# EEPROM.net
KiCad netlist of a schematic drawn in Altium Designer
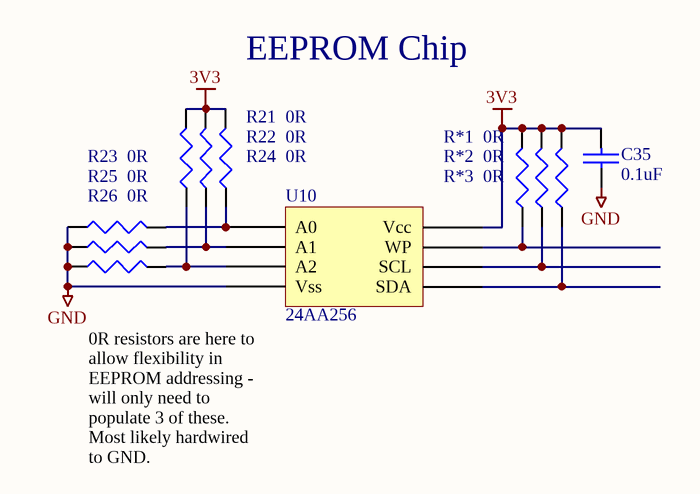
[diagram p0: EEPROM.SchDoc]

(export (version "E")
  (design (tool "Eeschema 10.0.6"))
  (components
    (comp (ref "C35")
      (value "0.1uF")
      (footprint "0805")
      (description "Capacitor")
      (libsource (lib "*") (part "CAP"))
    )
    (comp (ref "R*1")
      (value "0R")
      (footprint "0603")
      (description "Resistor")
      (libsource (lib "SunswiftLib20030312RR") (part "RES1"))
    )
    (comp (ref "R*2")
      (value "0R")
      (footprint "0603")
      (description "Resistor")
      (libsource (lib "SunswiftLib20030312RR") (part "RES1"))
    )
    (comp (ref "R*3")
      (value "0R")
      (footprint "0603")
      (description "Resistor")
      (libsource (lib "SunswiftLib20030312RR") (part "RES1"))
    )
    (comp (ref "R21")
      (value "0R")
      (footprint "0603")
      (description "Resistor")
      (libsource (lib "SunswiftLib20030312RR") (part "RES1"))
    )
    (comp (ref "R22")
      (value "0R")
      (footprint "0603")
      (description "Resistor")
      (libsource (lib "SunswiftLib20030312RR") (part "RES1"))
    )
    (comp (ref "R23")
      (value "0R")
      (footprint "0603")
      (description "Resistor")
      (libsource (lib "SunswiftLib20030312RR") (part "RES1"))
    )
    (comp (ref "R24")
      (value "0R")
      (footprint "0603")
      (description "Resistor")
      (libsource (lib "SunswiftLib20030312RR") (part "RES1"))
    )
    (comp (ref "R25")
      (value "0R")
      (footprint "0603")
      (description "Resistor")
      (libsource (lib "SunswiftLib20030312RR") (part "RES1"))
    )
    (comp (ref "R26")
      (value "0R")
      (footprint "0603")
      (description "Resistor")
      (libsource (lib "SunswiftLib20030312RR") (part "RES1"))
    )
    (comp (ref "U10") (value "24AA256") (footprint "DIP8") (libsource (lib "Miscellaneous") (part "24AA256")))
  )
  (nets
    (net (code "1") (name "3V3") (class "Default")
      (node (ref "C35") (pin "1") (pinfunction "1_1") (pintype "passive"))
      (node (ref "R*1") (pin "2") (pinfunction "2_2") (pintype "passive"))
      (node (ref "R*2") (pin "2") (pinfunction "2_2") (pintype "passive"))
      (node (ref "R*3") (pin "2") (pinfunction "2_2") (pintype "passive"))
      (node (ref "R21") (pin "2") (pinfunction "2_2") (pintype "passive"))
      (node (ref "R22") (pin "2") (pinfunction "2_2") (pintype "passive"))
      (node (ref "R24") (pin "2") (pinfunction "2_2") (pintype "passive"))
      (node (ref "U10") (pin "8") (pinfunction "Vcc_8") (pintype "passive"))
    )
    (net (code "2") (name "GND") (class "Default")
      (node (ref "C35") (pin "2") (pinfunction "2_2") (pintype "passive"))
      (node (ref "R23") (pin "1") (pinfunction "1_1") (pintype "passive"))
      (node (ref "R25") (pin "1") (pinfunction "1_1") (pintype "passive"))
      (node (ref "R26") (pin "1") (pinfunction "1_1") (pintype "passive"))
      (node (ref "U10") (pin "4") (pinfunction "Vss_4") (pintype "passive"))
    )
    (net (code "3") (name "Net-(U10-A0)") (class "Default")
      (node (ref "R21") (pin "1") (pinfunction "1_1") (pintype "passive"))
      (node (ref "R23") (pin "2") (pinfunction "2_2") (pintype "passive"))
      (node (ref "U10") (pin "1") (pinfunction "A0_1") (pintype "passive"))
    )
    (net (code "4") (name "Net-(U10-A1)") (class "Default")
      (node (ref "R22") (pin "1") (pinfunction "1_1") (pintype "passive"))
      (node (ref "R25") (pin "2") (pinfunction "2_2") (pintype "passive"))
      (node (ref "U10") (pin "2") (pinfunction "A1_2") (pintype "passive"))
    )
    (net (code "5") (name "Net-(U10-A2)") (class "Default")
      (node (ref "R24") (pin "1") (pinfunction "1_1") (pintype "passive"))
      (node (ref "R26") (pin "2") (pinfunction "2_2") (pintype "passive"))
      (node (ref "U10") (pin "3") (pinfunction "A2_3") (pintype "passive"))
    )
    (net (code "6") (name "Net-(U10-SCL)") (class "Default")
      (node (ref "R*2") (pin "1") (pinfunction "1_1") (pintype "passive"))
      (node (ref "U10") (pin "6") (pinfunction "SCL_6") (pintype "passive"))
    )
    (net (code "7") (name "Net-(U10-SDA)") (class "Default")
      (node (ref "R*1") (pin "1") (pinfunction "1_1") (pintype "passive"))
      (node (ref "U10") (pin "5") (pinfunction "SDA_5") (pintype "passive"))
    )
    (net (code "8") (name "Net-(U10-WP)") (class "Default")
      (node (ref "R*3") (pin "1") (pinfunction "1_1") (pintype "passive"))
      (node (ref "U10") (pin "7") (pinfunction "WP_7") (pintype "passive"))
    )
  )
)
